# MCU.net
KiCad netlist of a schematic drawn in Altium Designer
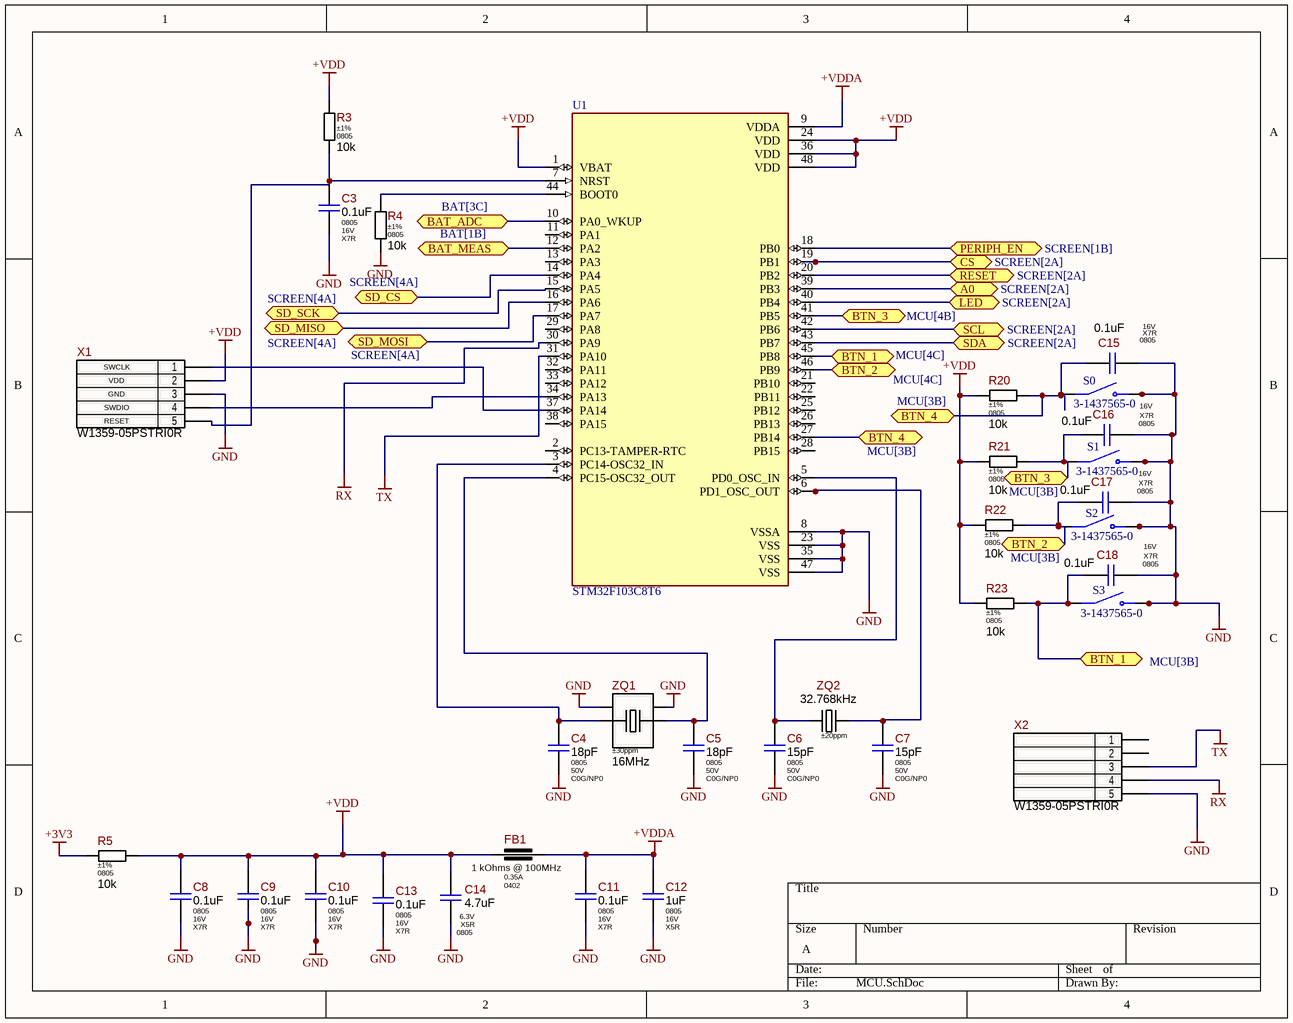
[diagram p0: MCU.SchDoc]

(export (version "E")
  (design (tool "Eeschema 10.0.6"))
  (components
    (comp (ref "C3")
      (value "0.1uF")
      (footprint "ALL:C0805")
      (fields
        (field (name "PACKAGE") "0805")
        (field (name "VOLTAGE") "16V")
        (field (name "DIELECTRIC TYPE") "X7R")
        (field (name "PART NUMBER") "GRM155R71C104JA88J")
        (field (name "MANUFACTURER") "Murata Electronics")
        (field (name "TOLERANCE") "±5%")
      )
      (libsource (lib "Miscellaneous Devices") (part "Capacitor-NonPolar"))
    )
    (comp (ref "C4")
      (value "18pF")
      (footprint "ALL:C0805")
      (description "18pF 50V C0G ±5% 0402 Ceramic Capacitor RoHS")
      (fields
        (field (name "PACKAGE") "0805")
        (field (name "VOLTAGE") "50V")
        (field (name "DIELECTRIC TYPE") "C0G/NP0")
        (field (name "PART NUMBER") "GRM1555C1H180JA01D")
        (field (name "MANUFACTURER") "Murata Electronics")
      )
      (libsource (lib "AjaxLibrary") (part "Capacitor-NonPolar"))
    )
    (comp (ref "C5")
      (value "18pF")
      (footprint "ALL:C0805")
      (fields
        (field (name "PACKAGE") "0805")
        (field (name "VOLTAGE") "50V")
        (field (name "DIELECTRIC TYPE") "C0G/NP0")
        (field (name "PART NUMBER") "GRM1555C1H180JA01D")
        (field (name "MANUFACTURER") "Murata Electronics")
        (field (name "TOLERANCE") "±5%")
      )
      (libsource (lib "Miscellaneous Devices") (part "Capacitor-NonPolar"))
    )
    (comp (ref "C6")
      (value "15pF")
      (footprint "ALL:C0805")
      (fields
        (field (name "PACKAGE") "0805")
        (field (name "VOLTAGE") "50V")
        (field (name "DIELECTRIC TYPE") "C0G/NP0")
        (field (name "PART NUMBER") "GRM1555C1H150FA01D")
        (field (name "MANUFACTURER") "Murata Electronics")
        (field (name "TOLERANCE") "±1%")
      )
      (libsource (lib "Miscellaneous Devices") (part "Capacitor-NonPolar"))
    )
    (comp (ref "C7")
      (value "15pF")
      (footprint "ALL:C0805")
      (description "15pF 50V C0G ±1% 0402 Ceramic Capacitor RoHS")
      (fields
        (field (name "PACKAGE") "0805")
        (field (name "VOLTAGE") "50V")
        (field (name "DIELECTRIC TYPE") "C0G/NP0")
        (field (name "PART NUMBER") "GRM1555C1H150FA01D")
        (field (name "MANUFACTURER") "Murata Electronics")
      )
      (libsource (lib "AjaxLibrary") (part "Capacitor-NonPolar"))
    )
    (comp (ref "C8")
      (value "0.1uF")
      (footprint "ALL:C0805")
      (fields
        (field (name "PACKAGE") "0805")
        (field (name "VOLTAGE") "16V")
        (field (name "DIELECTRIC TYPE") "X7R")
        (field (name "PART NUMBER") "GRM155R71C104JA88J")
        (field (name "MANUFACTURER") "Murata Electronics")
        (field (name "TOLERANCE") "±5%")
      )
      (libsource (lib "Miscellaneous Devices") (part "Capacitor-NonPolar"))
    )
    (comp (ref "C9")
      (value "0.1uF")
      (footprint "ALL:C0805")
      (fields
        (field (name "PACKAGE") "0805")
        (field (name "VOLTAGE") "16V")
        (field (name "DIELECTRIC TYPE") "X7R")
        (field (name "PART NUMBER") "GRM155R71C104JA88J")
        (field (name "MANUFACTURER") "Murata Electronics")
        (field (name "TOLERANCE") "±5%")
      )
      (libsource (lib "Miscellaneous Devices") (part "Capacitor-NonPolar"))
    )
    (comp (ref "C10")
      (value "0.1uF")
      (footprint "ALL:C0805")
      (fields
        (field (name "PACKAGE") "0805")
        (field (name "VOLTAGE") "16V")
        (field (name "DIELECTRIC TYPE") "X7R")
        (field (name "PART NUMBER") "GRM155R71C104JA88J")
        (field (name "MANUFACTURER") "Murata Electronics")
        (field (name "TOLERANCE") "±5%")
      )
      (libsource (lib "Miscellaneous Devices") (part "Capacitor-NonPolar"))
    )
    (comp (ref "C11")
      (value "0.1uF")
      (footprint "ALL:C0805")
      (fields
        (field (name "PACKAGE") "0805")
        (field (name "VOLTAGE") "16V")
        (field (name "DIELECTRIC TYPE") "X7R")
        (field (name "PART NUMBER") "GRM155R71C104JA88J")
        (field (name "MANUFACTURER") "Murata Electronics")
        (field (name "TOLERANCE") "±5%")
      )
      (libsource (lib "Miscellaneous Devices") (part "Capacitor-NonPolar"))
    )
    (comp (ref "C12")
      (value "1uF")
      (footprint "ALL:C0805")
      (fields
        (field (name "PACKAGE") "0805")
        (field (name "VOLTAGE") "16V")
        (field (name "DIELECTRIC TYPE") "X5R")
        (field (name "PART NUMBER") "CL05A105KO5NNNC")
        (field (name "MANUFACTURER") "Samsung Electro-Mechanics")
        (field (name "TOLERANCE") "±10%")
      )
      (libsource (lib "Miscellaneous Devices") (part "Capacitor-NonPolar"))
    )
    (comp (ref "C13")
      (value "0.1uF")
      (footprint "ALL:C0805")
      (fields
        (field (name "PACKAGE") "0805")
        (field (name "VOLTAGE") "16V")
        (field (name "DIELECTRIC TYPE") "X7R")
        (field (name "PART NUMBER") "GRM155R71C104JA88J")
        (field (name "MANUFACTURER") "Murata Electronics")
        (field (name "TOLERANCE") "±5%")
      )
      (libsource (lib "Miscellaneous Devices") (part "Capacitor-NonPolar"))
    )
    (comp (ref "C14")
      (value "4.7uF")
      (footprint "ALL:C0805")
      (fields
        (field (name "PACKAGE") "0805")
        (field (name "VOLTAGE") "6.3V")
        (field (name "DIELECTRIC TYPE") "X5R")
        (field (name "PART NUMBER") "GRM155R60J475ME47")
        (field (name "MANUFACTURER") "Murata Electronics")
        (field (name "TOLERANCE") "±20%")
      )
      (libsource (lib "Miscellaneous Devices") (part "Capacitor-NonPolar"))
    )
    (comp (ref "C15")
      (value "0.1uF")
      (footprint "ALL:C0805")
      (fields
        (field (name "PACKAGE") "0805")
        (field (name "VOLTAGE") "16V")
        (field (name "DIELECTRIC TYPE") "X7R")
        (field (name "PART NUMBER") "GRM155R71C104JA88J")
        (field (name "MANUFACTURER") "Murata Electronics")
        (field (name "TOLERANCE") "±5%")
      )
      (libsource (lib "Miscellaneous Devices") (part "Capacitor-NonPolar"))
    )
    (comp (ref "C16")
      (value "0.1uF")
      (footprint "ALL:C0805")
      (fields
        (field (name "PACKAGE") "0805")
        (field (name "VOLTAGE") "16V")
        (field (name "DIELECTRIC TYPE") "X7R")
        (field (name "PART NUMBER") "GRM155R71C104JA88J")
        (field (name "MANUFACTURER") "Murata Electronics")
        (field (name "TOLERANCE") "±5%")
      )
      (libsource (lib "Miscellaneous Devices") (part "Capacitor-NonPolar"))
    )
    (comp (ref "C17")
      (value "0.1uF")
      (footprint "ALL:C0805")
      (fields
        (field (name "PACKAGE") "0805")
        (field (name "VOLTAGE") "16V")
        (field (name "DIELECTRIC TYPE") "X7R")
        (field (name "PART NUMBER") "GRM155R71C104JA88J")
        (field (name "MANUFACTURER") "Murata Electronics")
        (field (name "TOLERANCE") "±5%")
      )
      (libsource (lib "Miscellaneous Devices") (part "Capacitor-NonPolar"))
    )
    (comp (ref "C18")
      (value "0.1uF")
      (footprint "ALL:C0805")
      (fields
        (field (name "PACKAGE") "0805")
        (field (name "VOLTAGE") "16V")
        (field (name "DIELECTRIC TYPE") "X7R")
        (field (name "PART NUMBER") "GRM155R71C104JA88J")
        (field (name "MANUFACTURER") "Murata Electronics")
        (field (name "TOLERANCE") "±5%")
      )
      (libsource (lib "Miscellaneous Devices") (part "Capacitor-NonPolar"))
    )
    (comp (ref "FB1")
      (value "1 kOhms @ 100MHz")
      (footprint "ALL:Ferrite_Beard")
      (description "1 kOhms @ 100MHz Ferrite Bead 0402, 350mA 490mOhm")
      (fields
        (field (name "CURRENT") "0.35A")
        (field (name "PACKAGE") "0402")
        (field (name "PART NUMBER") "BLM15AX102SN1D")
        (field (name "TOLERANCE") "±25%")
      )
      (libsource (lib "AjaxLibrary") (part "Ferrite-Bead"))
    )
    (comp (ref "R3")
      (value "10k")
      (footprint "R0805")
      (description "10 kOhms ±1% 1/16W 0402 Thick Film Resistor")
      (fields
        (field (name "TOLERANCE") "±1%")
        (field (name "PACKAGE") "0805")
        (field (name "PART NUMBER") "RC0402FR-0710KL")
        (field (name "MANUFACTURER") "Yageo")
      )
      (libsource (lib "Miscellaneous Devices") (part "Resistor"))
    )
    (comp (ref "R4")
      (value "10k")
      (footprint "R0805")
      (description "10 kOhms ±1% 1/16W 0402 Thick Film Resistor")
      (fields
        (field (name "TOLERANCE") "±1%")
        (field (name "PACKAGE") "0805")
        (field (name "PART NUMBER") "RC0402FR-0710KL")
        (field (name "MANUFACTURER") "Yageo")
      )
      (libsource (lib "Miscellaneous Devices") (part "Resistor"))
    )
    (comp (ref "R5")
      (value "10k")
      (footprint "R0805")
      (description "10 kOhms ±1% 1/16W 0402 Thick Film Resistor")
      (fields
        (field (name "TOLERANCE") "±1%")
        (field (name "PACKAGE") "0805")
        (field (name "PART NUMBER") "RC0402FR-0710KL")
        (field (name "MANUFACTURER") "Yageo")
      )
      (libsource (lib "Miscellaneous Devices") (part "Resistor"))
    )
    (comp (ref "R20")
      (value "10k")
      (footprint "R0805")
      (description "10 kOhms ±1% 1/16W 0402 Thick Film Resistor")
      (fields
        (field (name "TOLERANCE") "±1%")
        (field (name "PACKAGE") "0805")
        (field (name "PART NUMBER") "RC0402FR-0710KL")
        (field (name "MANUFACTURER") "Yageo")
      )
      (libsource (lib "Miscellaneous Devices") (part "Resistor"))
    )
    (comp (ref "R21")
      (value "10k")
      (footprint "R0805")
      (description "10 kOhms ±1% 1/16W 0402 Thick Film Resistor")
      (fields
        (field (name "TOLERANCE") "±1%")
        (field (name "PACKAGE") "0805")
        (field (name "PART NUMBER") "RC0402FR-0710KL")
        (field (name "MANUFACTURER") "Yageo")
      )
      (libsource (lib "Miscellaneous Devices") (part "Resistor"))
    )
    (comp (ref "R22")
      (value "10k")
      (footprint "R0805")
      (description "10 kOhms ±1% 1/16W 0402 Thick Film Resistor")
      (fields
        (field (name "TOLERANCE") "±1%")
        (field (name "PACKAGE") "0805")
        (field (name "PART NUMBER") "RC0402FR-0710KL")
        (field (name "MANUFACTURER") "Yageo")
      )
      (libsource (lib "Miscellaneous Devices") (part "Resistor"))
    )
    (comp (ref "R23")
      (value "10k")
      (footprint "R0805")
      (description "10 kOhms ±1% 1/16W 0402 Thick Film Resistor")
      (fields
        (field (name "TOLERANCE") "±1%")
        (field (name "PACKAGE") "0805")
        (field (name "PART NUMBER") "RC0402FR-0710KL")
        (field (name "MANUFACTURER") "Yageo")
      )
      (libsource (lib "Miscellaneous Devices") (part "Resistor"))
    )
    (comp (ref "S0")
      (value "3-1437565-0")
      (footprint "SW_3-1437565-0")
      (description "Switch Tactile OFF (ON) SPST Round Button Gull Wing 0.05A 24VDC 1VA 9.18N SMD T/R")
      (fields (field (name "MF") "TE Connectivity"))
      (libsource (lib "3-1437565-0") (part "3-1437565-0"))
    )
    (comp (ref "S1")
      (value "3-1437565-0")
      (footprint "SW_3-1437565-0")
      (description "Switch Tactile OFF (ON) SPST Round Button Gull Wing 0.05A 24VDC 1VA 9.18N SMD T/R")
      (fields (field (name "MF") "TE Connectivity"))
      (libsource (lib "3-1437565-0") (part "3-1437565-0"))
    )
    (comp (ref "S2")
      (value "3-1437565-0")
      (footprint "SW_3-1437565-0")
      (description "Switch Tactile OFF (ON) SPST Round Button Gull Wing 0.05A 24VDC 1VA 9.18N SMD T/R")
      (fields (field (name "MF") "TE Connectivity"))
      (libsource (lib "3-1437565-0") (part "3-1437565-0"))
    )
    (comp (ref "S3")
      (value "3-1437565-0")
      (footprint "SW_3-1437565-0")
      (description "Switch Tactile OFF (ON) SPST Round Button Gull Wing 0.05A 24VDC 1VA 9.18N SMD T/R")
      (fields (field (name "MF") "TE Connectivity"))
      (libsource (lib "3-1437565-0") (part "3-1437565-0"))
    )
    (comp (ref "U1")
      (value "STM32F103C8T6")
      (footprint "QFP50P900X900X160-48N")
      (description "ARM® Cortex®-M3 STM32F1 Microcontroller IC 32-Bit 72MHz 64KB (64K x 8) FLASH 48-LQFP (7x7)")
      (fields (field (name "MF") "STMicroelectronics"))
      (libsource (lib "STM32F103C8T6(2)") (part "STM32F103C8T6"))
    )
    (comp (ref "X1")
      (value "W1359-05PSTRI0R")
      (footprint "ALL:DBG_PINS")
      (description "1.25mm Wire-to-Board Header, Vertical, PTH, 5 pin")
      (fields
        (field (name "PART NUMBER") "W1359-05PSTRI0R")
        (field (name "MANUFACTURER") "Hsuan Mao Technology")
      )
      (libsource (lib "Miscellaneous Connectors") (part "General-5-Pin"))
    )
    (comp (ref "X2")
      (value "W1359-05PSTRI0R")
      (footprint "ALL:DBG_PINS")
      (description "1.25mm Wire-to-Board Header, Vertical, PTH, 5 pin")
      (fields
        (field (name "PART NUMBER") "W1359-05PSTRI0R")
        (field (name "MANUFACTURER") "Hsuan Mao Technology")
      )
      (libsource (lib "Miscellaneous Connectors") (part "General-5-Pin"))
    )
    (comp (ref "ZQ1")
      (value "CXA-016000-3X7X40")
      (footprint "ALL:Crystal16Mhz")
      (fields
        (field (name "FREQUENCY TOLERANCE") "±30ppm")
        (field (name "FREQUENCY") "16MHz")
        (field (name "MANUFACTURER") "Aker")
      )
      (libsource (lib "Miscellaneous Devices") (part "Crystal-Quartz-4-Pin-01"))
    )
    (comp (ref "ZQ2")
      (value "D31-032768-BDRD4A")
      (footprint "ALL:Crystal32768")
      (description "32.768kHz 12.5pF ±20ppm, 0.5uW DL Crystal Quartz")
      (fields
        (field (name "FREQUENCY TOLERANCE") "±20ppm")
        (field (name "FREQUENCY") "32.768kHz")
        (field (name "MANUFACTURER") "Aker")
      )
      (libsource (lib "AjaxLibrary") (part "Crystal-Quartz-01"))
    )
  )
  (nets
    (net (code "1") (name "+3V3") (class "Default") (node (ref "R5") (pin "1") (pintype "passive")))
    (net (code "2") (name "+VDD") (class "Default")
      (node (ref "C10") (pin "1") (pinfunction "1_1") (pintype "passive"))
      (node (ref "C13") (pin "1") (pinfunction "1_1") (pintype "passive"))
      (node (ref "C14") (pin "1") (pinfunction "1_1") (pintype "passive"))
      (node (ref "C8") (pin "1") (pinfunction "1_1") (pintype "passive"))
      (node (ref "C9") (pin "1") (pinfunction "1_1") (pintype "passive"))
      (node (ref "FB1") (pin "2") (pintype "passive"))
      (node (ref "R20") (pin "1") (pintype "passive"))
      (node (ref "R21") (pin "1") (pintype "passive"))
      (node (ref "R22") (pin "1") (pintype "passive"))
      (node (ref "R23") (pin "1") (pintype "passive"))
      (node (ref "R3") (pin "1") (pintype "passive"))
      (node (ref "R5") (pin "2") (pintype "passive"))
      (node (ref "U1") (pin "1") (pinfunction "VBAT_1") (pintype "bidirectional"))
      (node (ref "U1") (pin "24") (pinfunction "VDD_24") (pintype "power_in"))
      (node (ref "U1") (pin "36") (pinfunction "VDD_36") (pintype "power_in"))
      (node (ref "U1") (pin "48") (pinfunction "VDD_48") (pintype "power_in"))
      (node (ref "X1") (pin "2") (pinfunction "2_2") (pintype "passive"))
    )
    (net (code "3") (name "+VDDA") (class "Default")
      (node (ref "C11") (pin "1") (pinfunction "1_1") (pintype "passive"))
      (node (ref "C12") (pin "1") (pinfunction "1_1") (pintype "passive"))
      (node (ref "FB1") (pin "1") (pintype "passive"))
      (node (ref "U1") (pin "9") (pinfunction "VDDA_9") (pintype "power_in"))
    )
    (net (code "4") (name "/A0") (class "Default")
      (node (ref "U1") (pin "39") (pinfunction "PB3_39") (pintype "bidirectional"))
    )
    (net (code "5") (name "/BAT_ADC") (class "Default")
      (node (ref "U1") (pin "10") (pinfunction "PA0_WKUP_10") (pintype "bidirectional"))
    )
    (net (code "6") (name "/BAT_MEAS") (class "Default")
      (node (ref "U1") (pin "12") (pinfunction "PA2_12") (pintype "bidirectional"))
    )
    (net (code "7") (name "/BTN_1") (class "Default")
      (node (ref "C18") (pin "1") (pinfunction "1_1") (pintype "passive"))
      (node (ref "R23") (pin "2") (pintype "passive"))
      (node (ref "S3") (pin "1") (pinfunction "COM_1") (pintype "passive"))
      (node (ref "S3") (pin "2") (pinfunction "COM_2") (pintype "passive"))
      (node (ref "U1") (pin "45") (pinfunction "PB8_45") (pintype "bidirectional"))
    )
    (net (code "8") (name "/BTN_2") (class "Default")
      (node (ref "C17") (pin "1") (pinfunction "1_1") (pintype "passive"))
      (node (ref "R22") (pin "2") (pintype "passive"))
      (node (ref "S2") (pin "1") (pinfunction "COM_1") (pintype "passive"))
      (node (ref "S2") (pin "2") (pinfunction "COM_2") (pintype "passive"))
      (node (ref "U1") (pin "46") (pinfunction "PB9_46") (pintype "bidirectional"))
    )
    (net (code "9") (name "/BTN_3") (class "Default")
      (node (ref "C16") (pin "1") (pinfunction "1_1") (pintype "passive"))
      (node (ref "R21") (pin "2") (pintype "passive"))
      (node (ref "S1") (pin "1") (pinfunction "COM_1") (pintype "passive"))
      (node (ref "S1") (pin "2") (pinfunction "COM_2") (pintype "passive"))
      (node (ref "U1") (pin "41") (pinfunction "PB5_41") (pintype "bidirectional"))
    )
    (net (code "10") (name "/BTN_4") (class "Default")
      (node (ref "C15") (pin "1") (pinfunction "1_1") (pintype "passive"))
      (node (ref "R20") (pin "2") (pintype "passive"))
      (node (ref "S0") (pin "1") (pinfunction "COM_1") (pintype "passive"))
      (node (ref "S0") (pin "2") (pinfunction "COM_2") (pintype "passive"))
      (node (ref "U1") (pin "27") (pinfunction "PB14_27") (pintype "bidirectional"))
    )
    (net (code "11") (name "/CS") (class "Default")
      (node (ref "U1") (pin "19") (pinfunction "PB1_19") (pintype "bidirectional"))
    )
    (net (code "12") (name "/LED") (class "Default")
      (node (ref "U1") (pin "40") (pinfunction "PB4_40") (pintype "bidirectional"))
    )
    (net (code "13") (name "/PERIPH_EN") (class "Default")
      (node (ref "U1") (pin "18") (pinfunction "PB0_18") (pintype "bidirectional"))
    )
    (net (code "14") (name "/RESET") (class "Default")
      (node (ref "U1") (pin "20") (pinfunction "PB2_20") (pintype "bidirectional"))
    )
    (net (code "15") (name "/SCL") (class "Default")
      (node (ref "U1") (pin "42") (pinfunction "PB6_42") (pintype "bidirectional"))
    )
    (net (code "16") (name "/SDA") (class "Default")
      (node (ref "U1") (pin "43") (pinfunction "PB7_43") (pintype "bidirectional"))
    )
    (net (code "17") (name "/SD_CS") (class "Default")
      (node (ref "U1") (pin "14") (pinfunction "PA4_14") (pintype "bidirectional"))
    )
    (net (code "18") (name "/SD_MISO") (class "Default")
      (node (ref "U1") (pin "16") (pinfunction "PA6_16") (pintype "bidirectional"))
    )
    (net (code "19") (name "/SD_MOSI") (class "Default")
      (node (ref "U1") (pin "17") (pinfunction "PA7_17") (pintype "bidirectional"))
    )
    (net (code "20") (name "/SD_SCK") (class "Default")
      (node (ref "U1") (pin "15") (pinfunction "PA5_15") (pintype "bidirectional"))
    )
    (net (code "21") (name "GND") (class "Default")
      (node (ref "C10") (pin "2") (pinfunction "2_2") (pintype "passive"))
      (node (ref "C11") (pin "2") (pinfunction "2_2") (pintype "passive"))
      (node (ref "C12") (pin "2") (pinfunction "2_2") (pintype "passive"))
      (node (ref "C13") (pin "2") (pinfunction "2_2") (pintype "passive"))
      (node (ref "C14") (pin "2") (pinfunction "2_2") (pintype "passive"))
      (node (ref "C15") (pin "2") (pinfunction "2_2") (pintype "passive"))
      (node (ref "C16") (pin "2") (pinfunction "2_2") (pintype "passive"))
      (node (ref "C17") (pin "2") (pinfunction "2_2") (pintype "passive"))
      (node (ref "C18") (pin "2") (pinfunction "2_2") (pintype "passive"))
      (node (ref "C3") (pin "2") (pinfunction "2_2") (pintype "passive"))
      (node (ref "C4") (pin "2") (pinfunction "2_2") (pintype "passive"))
      (node (ref "C5") (pin "2") (pinfunction "2_2") (pintype "passive"))
      (node (ref "C6") (pin "2") (pinfunction "2_2") (pintype "passive"))
      (node (ref "C7") (pin "2") (pinfunction "2_2") (pintype "passive"))
      (node (ref "C8") (pin "2") (pinfunction "2_2") (pintype "passive"))
      (node (ref "C9") (pin "2") (pinfunction "2_2") (pintype "passive"))
      (node (ref "R4") (pin "2") (pintype "passive"))
      (node (ref "S0") (pin "3") (pinfunction "NO_3") (pintype "passive"))
      (node (ref "S0") (pin "4") (pinfunction "NO_4") (pintype "passive"))
      (node (ref "S1") (pin "3") (pinfunction "NO_3") (pintype "passive"))
      (node (ref "S1") (pin "4") (pinfunction "NO_4") (pintype "passive"))
      (node (ref "S2") (pin "3") (pinfunction "NO_3") (pintype "passive"))
      (node (ref "S2") (pin "4") (pinfunction "NO_4") (pintype "passive"))
      (node (ref "S3") (pin "3") (pinfunction "NO_3") (pintype "passive"))
      (node (ref "S3") (pin "4") (pinfunction "NO_4") (pintype "passive"))
      (node (ref "U1") (pin "23") (pinfunction "VSS_23") (pintype "power_in"))
      (node (ref "U1") (pin "35") (pinfunction "VSS_35") (pintype "power_in"))
      (node (ref "U1") (pin "47") (pinfunction "VSS_47") (pintype "power_in"))
      (node (ref "U1") (pin "8") (pinfunction "VSSA_8") (pintype "power_in"))
      (node (ref "X1") (pin "3") (pinfunction "3_3") (pintype "passive"))
      (node (ref "X2") (pin "5") (pinfunction "5_5") (pintype "passive"))
      (node (ref "ZQ1") (pin "2") (pinfunction "NC1_2") (pintype "passive"))
      (node (ref "ZQ1") (pin "4") (pinfunction "NC2_4") (pintype "passive"))
    )
    (net (code "22") (name "Net-(U1-BOOT0)") (class "Default")
      (node (ref "R4") (pin "1") (pintype "passive"))
      (node (ref "U1") (pin "44") (pinfunction "BOOT0_44") (pintype "input"))
    )
    (net (code "23") (name "Net-(U1-NRST)") (class "Default")
      (node (ref "C3") (pin "1") (pinfunction "1_1") (pintype "passive"))
      (node (ref "R3") (pin "2") (pintype "passive"))
      (node (ref "U1") (pin "7") (pinfunction "NRST_7") (pintype "input"))
      (node (ref "X1") (pin "5") (pinfunction "5_5") (pintype "passive"))
    )
    (net (code "24") (name "Net-(U1-PA13)") (class "Default")
      (node (ref "U1") (pin "34") (pinfunction "PA13_34") (pintype "bidirectional"))
      (node (ref "X1") (pin "4") (pinfunction "4_4") (pintype "passive"))
    )
    (net (code "25") (name "Net-(U1-PA14)") (class "Default")
      (node (ref "U1") (pin "37") (pinfunction "PA14_37") (pintype "bidirectional"))
      (node (ref "X1") (pin "1") (pinfunction "1_1") (pintype "passive"))
    )
    (net (code "26") (name "Net-(U1-PC14-OSC32_IN)") (class "Default")
      (node (ref "C4") (pin "1") (pinfunction "1_1") (pintype "passive"))
      (node (ref "U1") (pin "3") (pinfunction "PC14-OSC32_IN_3") (pintype "bidirectional"))
      (node (ref "ZQ1") (pin "1") (pinfunction "XTAL1_1") (pintype "passive"))
    )
    (net (code "27") (name "Net-(U1-PC15-OSC32_OUT)") (class "Default")
      (node (ref "C5") (pin "1") (pinfunction "1_1") (pintype "passive"))
      (node (ref "U1") (pin "4") (pinfunction "PC15-OSC32_OUT_4") (pintype "bidirectional"))
      (node (ref "ZQ1") (pin "3") (pinfunction "XTAL2_3") (pintype "passive"))
    )
    (net (code "28") (name "Net-(U1-PD0_OSC_IN)") (class "Default")
      (node (ref "C6") (pin "1") (pinfunction "1_1") (pintype "passive"))
      (node (ref "U1") (pin "5") (pinfunction "PD0_OSC_IN_5") (pintype "bidirectional"))
      (node (ref "ZQ2") (pin "1") (pinfunction "XTAL1_1") (pintype "passive"))
    )
    (net (code "29") (name "Net-(U1-PD1_OSC_OUT)") (class "Default")
      (node (ref "C7") (pin "1") (pinfunction "1_1") (pintype "passive"))
      (node (ref "U1") (pin "6") (pinfunction "PD1_OSC_OUT_6") (pintype "bidirectional"))
      (node (ref "ZQ2") (pin "2") (pinfunction "XTAL2_2") (pintype "passive"))
    )
    (net (code "30") (name "RX") (class "Default")
      (node (ref "U1") (pin "30") (pinfunction "PA9_30") (pintype "bidirectional"))
      (node (ref "X2") (pin "4") (pinfunction "4_4") (pintype "passive"))
    )
    (net (code "31") (name "TX") (class "Default")
      (node (ref "U1") (pin "31") (pinfunction "PA10_31") (pintype "bidirectional"))
      (node (ref "X2") (pin "3") (pinfunction "3_3") (pintype "passive"))
    )
    (net (code "32") (name "unconnected-(U1-PA1-Pad11)") (class "Default")
      (node (ref "U1") (pin "11") (pinfunction "PA1_11") (pintype "bidirectional"))
    )
    (net (code "33") (name "unconnected-(U1-PA3-Pad13)") (class "Default")
      (node (ref "U1") (pin "13") (pinfunction "PA3_13") (pintype "bidirectional"))
    )
    (net (code "34") (name "unconnected-(U1-PA8-Pad29)") (class "Default")
      (node (ref "U1") (pin "29") (pinfunction "PA8_29") (pintype "bidirectional"))
    )
    (net (code "35") (name "unconnected-(U1-PA11-Pad32)") (class "Default")
      (node (ref "U1") (pin "32") (pinfunction "PA11_32") (pintype "bidirectional"))
    )
    (net (code "36") (name "unconnected-(U1-PA12-Pad33)") (class "Default")
      (node (ref "U1") (pin "33") (pinfunction "PA12_33") (pintype "bidirectional"))
    )
    (net (code "37") (name "unconnected-(U1-PA15-Pad38)") (class "Default")
      (node (ref "U1") (pin "38") (pinfunction "PA15_38") (pintype "bidirectional"))
    )
    (net (code "38") (name "unconnected-(U1-PB10-Pad21)") (class "Default")
      (node (ref "U1") (pin "21") (pinfunction "PB10_21") (pintype "bidirectional"))
    )
    (net (code "39") (name "unconnected-(U1-PB11-Pad22)") (class "Default")
      (node (ref "U1") (pin "22") (pinfunction "PB11_22") (pintype "bidirectional"))
    )
    (net (code "40") (name "unconnected-(U1-PB12-Pad25)") (class "Default")
      (node (ref "U1") (pin "25") (pinfunction "PB12_25") (pintype "bidirectional"))
    )
    (net (code "41") (name "unconnected-(U1-PB13-Pad26)") (class "Default")
      (node (ref "U1") (pin "26") (pinfunction "PB13_26") (pintype "bidirectional"))
    )
    (net (code "42") (name "unconnected-(U1-PB15-Pad28)") (class "Default")
      (node (ref "U1") (pin "28") (pinfunction "PB15_28") (pintype "bidirectional"))
    )
    (net (code "43") (name "unconnected-(U1-PC13-TAMPER-RTC-Pad2)") (class "Default")
      (node (ref "U1") (pin "2") (pinfunction "PC13-TAMPER-RTC_2") (pintype "bidirectional"))
    )
    (net (code "44") (name "unconnected-(X2-Pad1)") (class "Default")
      (node (ref "X2") (pin "1") (pinfunction "1_1") (pintype "passive"))
    )
    (net (code "45") (name "unconnected-(X2-Pad2)") (class "Default")
      (node (ref "X2") (pin "2") (pinfunction "2_2") (pintype "passive"))
    )
  )
)
